# REV001.net
KiCad netlist of a schematic drawn in EAGLE
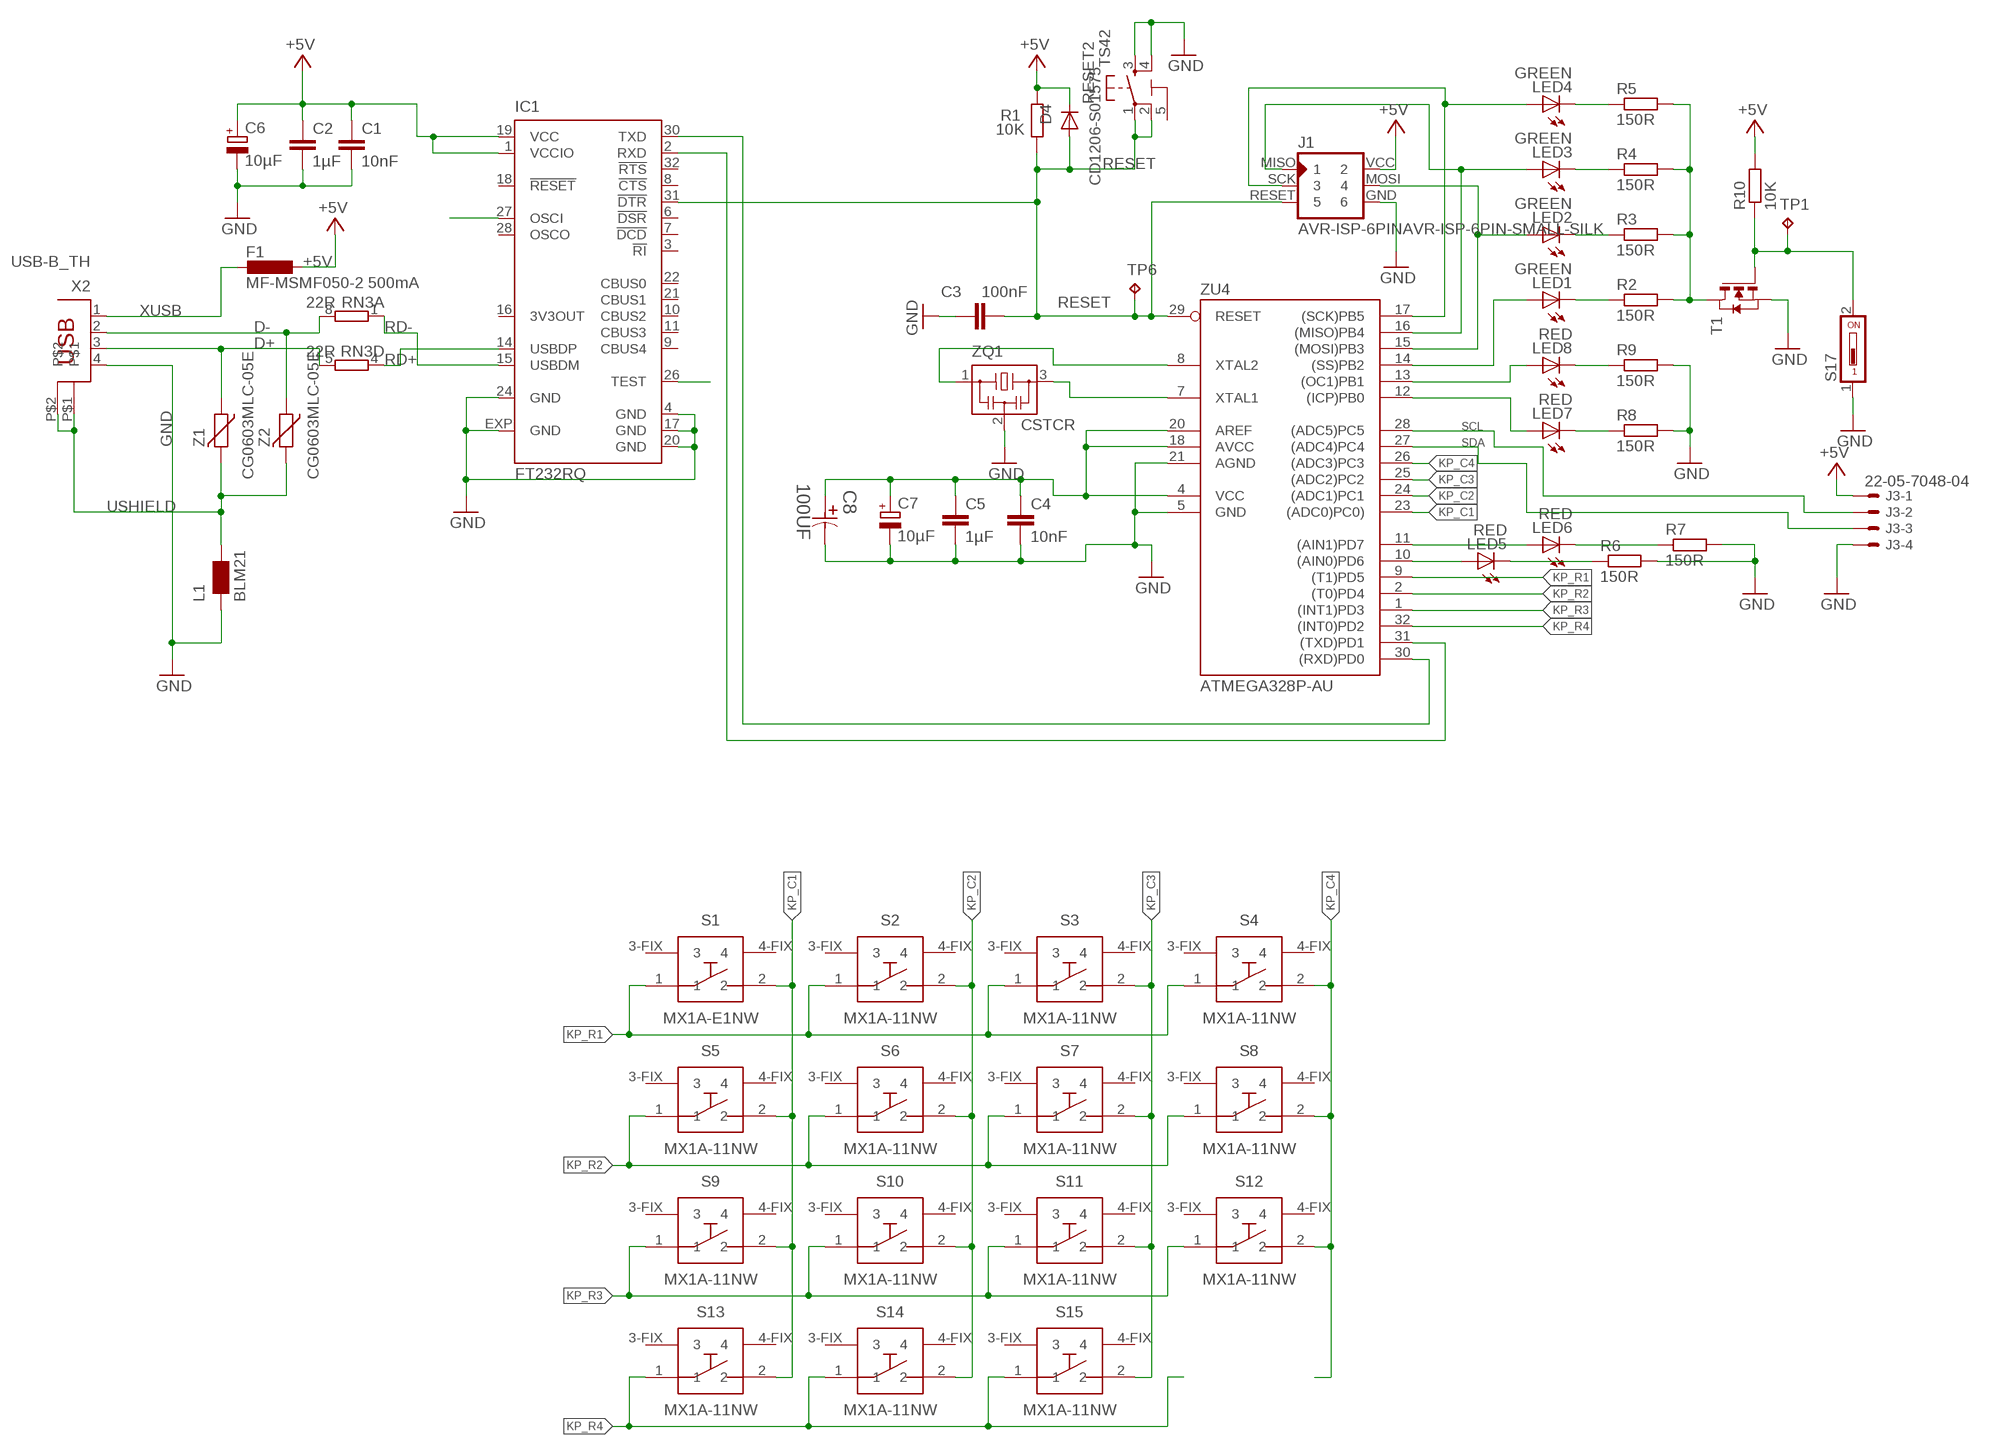
[diagram p0: schematic, sheet 1]

(export (version "E")
  (design (tool "Eeschema 10.0.6"))
  (components
    (comp (ref "C1")
      (value "10nF")
      (footprint "eagle-import:C0603K")
      (libsource (lib "eagle-import") (part "rcl_C-EUC0603K"))
    )
    (comp (ref "C2")
      (value "1µF")
      (footprint "eagle-import:C0603K")
      (libsource (lib "eagle-import") (part "rcl_C-EUC0603K"))
    )
    (comp (ref "C3")
      (value "100nF")
      (footprint "eagle-import:C0603-ROUND")
      (libsource (lib "eagle-import") (part "C-EUC0603"))
    )
    (comp (ref "C4")
      (value "10nF")
      (footprint "eagle-import:C0603K")
      (libsource (lib "eagle-import") (part "rcl_C-EUC0603K"))
    )
    (comp (ref "C5")
      (value "1µF")
      (footprint "eagle-import:C0603K")
      (libsource (lib "eagle-import") (part "rcl_C-EUC0603K"))
    )
    (comp (ref "C6")
      (value "10µF")
      (footprint "eagle-import:SMC_B")
      (libsource (lib "eagle-import") (part "CPOL-EUSMCB"))
    )
    (comp (ref "C7")
      (value "10µF")
      (footprint "eagle-import:SMC_B")
      (libsource (lib "eagle-import") (part "CPOL-EUSMCB"))
    )
    (comp (ref "C8")
      (value "100UF")
      (footprint "eagle-import:CAPAE430X610N")
      (fields (field (name "MPN") "EEE-FT0J101AR ") (field (name "TOLERANCE") "±20 %"))
      (libsource (lib "eagle-import") (part "EEE--CASE-BFT0J101AR"))
    )
    (comp (ref "D4")
      (value "CD1206-S01575")
      (footprint "eagle-import:MINIMELF")
      (libsource (lib "eagle-import") (part "DIODE-MINIMELF"))
    )
    (comp (ref "F1")
      (value "MF-MSMF050-2 500mA")
      (footprint "eagle-import:L1812")
      (libsource (lib "eagle-import") (part "L-EUL1812"))
    )
    (comp (ref "IC1")
      (value "FT232RQ")
      (footprint "eagle-import:QFN32")
      (libsource (lib "eagle-import") (part "FT232RQ"))
    )
    (comp (ref "J1")
      (value "AVR-ISP-6PINAVR-ISP-6PIN-SMALL-SILK")
      (footprint "eagle-import:AVR-ISP-6PIN-SMAILL-SILK")
      (libsource (lib "eagle-import") (part "AVR-ISP-6PINAVR-ISP-6PIN-SMALL-SILK"))
    )
    (comp (ref "J3")
      (value "22-05-7048-04")
      (footprint "eagle-import:7395-04")
      (libsource (lib "eagle-import") (part "22-?-0405-7048"))
    )
    (comp (ref "L1")
      (value "BLM21")
      (footprint "eagle-import:0805")
      (libsource (lib "eagle-import") (part "WE-CBF_0805"))
    )
    (comp (ref "LED1")
      (value "GREEN")
      (footprint "eagle-import:P-LCC-2")
      (libsource (lib "eagle-import") (part "LEDP-LCC-2"))
    )
    (comp (ref "LED2")
      (value "GREEN")
      (footprint "eagle-import:P-LCC-2")
      (libsource (lib "eagle-import") (part "LEDP-LCC-2"))
    )
    (comp (ref "LED3")
      (value "GREEN")
      (footprint "eagle-import:P-LCC-2")
      (libsource (lib "eagle-import") (part "LEDP-LCC-2"))
    )
    (comp (ref "LED4")
      (value "GREEN")
      (footprint "eagle-import:P-LCC-2")
      (libsource (lib "eagle-import") (part "LEDP-LCC-2"))
    )
    (comp (ref "LED5")
      (value "RED")
      (footprint "eagle-import:P-LCC-2")
      (libsource (lib "eagle-import") (part "LEDP-LCC-2"))
    )
    (comp (ref "LED6")
      (value "RED")
      (footprint "eagle-import:P-LCC-2")
      (libsource (lib "eagle-import") (part "LEDP-LCC-2"))
    )
    (comp (ref "LED7")
      (value "RED")
      (footprint "eagle-import:P-LCC-2")
      (libsource (lib "eagle-import") (part "LEDP-LCC-2"))
    )
    (comp (ref "LED8")
      (value "RED")
      (footprint "eagle-import:P-LCC-2")
      (libsource (lib "eagle-import") (part "LEDP-LCC-2"))
    )
    (comp (ref "R1")
      (value "10K")
      (footprint "eagle-import:R0805")
      (libsource (lib "eagle-import") (part "R-EU_R0805"))
    )
    (comp (ref "R2")
      (value "150R")
      (footprint "eagle-import:R0805")
      (libsource (lib "eagle-import") (part "rcl_R-EU_R0805"))
    )
    (comp (ref "R3")
      (value "150R")
      (footprint "eagle-import:R0805")
      (libsource (lib "eagle-import") (part "rcl_R-EU_R0805"))
    )
    (comp (ref "R4")
      (value "150R")
      (footprint "eagle-import:R0805")
      (libsource (lib "eagle-import") (part "rcl_R-EU_R0805"))
    )
    (comp (ref "R5")
      (value "150R")
      (footprint "eagle-import:R0805")
      (libsource (lib "eagle-import") (part "rcl_R-EU_R0805"))
    )
    (comp (ref "R6")
      (value "150R")
      (footprint "eagle-import:R0805")
      (libsource (lib "eagle-import") (part "rcl_R-EU_R0805"))
    )
    (comp (ref "R7")
      (value "150R")
      (footprint "eagle-import:R0805")
      (libsource (lib "eagle-import") (part "rcl_R-EU_R0805"))
    )
    (comp (ref "R8")
      (value "150R")
      (footprint "eagle-import:R0805")
      (libsource (lib "eagle-import") (part "rcl_R-EU_R0805"))
    )
    (comp (ref "R9")
      (value "150R")
      (footprint "eagle-import:R0805")
      (libsource (lib "eagle-import") (part "rcl_R-EU_R0805"))
    )
    (comp (ref "R10")
      (value "10K")
      (footprint "eagle-import:R0805")
      (libsource (lib "eagle-import") (part "rcl_R-EU_R0805"))
    )
    (comp (ref "RESET2")
      (value "TS42")
      (footprint "eagle-import:TS42")
      (libsource (lib "eagle-import") (part "TS42"))
    )
    (comp (ref "RN3")
      (value "22R")
      (footprint "eagle-import:CAY16")
      (libsource (lib "eagle-import") (part "4R-NCAY16"))
    )
    (comp (ref "S1")
      (value "MX1A-E1NW")
      (footprint "eagle-import:MX1A-11NW_1")
      (fields (field (name "MANUFACTURER_PART_NUMBER") "MX1A-11NW"))
      (libsource (lib "eagle-import") (part "MX1A-11NW"))
    )
    (comp (ref "S2")
      (value "MX1A-11NW")
      (footprint "eagle-import:MX1A-11NW_1")
      (libsource (lib "eagle-import") (part "MX1A-11NW"))
    )
    (comp (ref "S3")
      (value "MX1A-11NW")
      (footprint "eagle-import:MX1A-11NW_1")
      (libsource (lib "eagle-import") (part "MX1A-11NW"))
    )
    (comp (ref "S4")
      (value "MX1A-11NW")
      (footprint "eagle-import:MX1A-11NW_1")
      (libsource (lib "eagle-import") (part "MX1A-11NW"))
    )
    (comp (ref "S5")
      (value "MX1A-11NW")
      (footprint "eagle-import:MX1A-11NW_1")
      (libsource (lib "eagle-import") (part "MX1A-11NW"))
    )
    (comp (ref "S6")
      (value "MX1A-11NW")
      (footprint "eagle-import:MX1A-11NW_1")
      (libsource (lib "eagle-import") (part "MX1A-11NW"))
    )
    (comp (ref "S7")
      (value "MX1A-11NW")
      (footprint "eagle-import:MX1A-11NW_1")
      (libsource (lib "eagle-import") (part "MX1A-11NW"))
    )
    (comp (ref "S8")
      (value "MX1A-11NW")
      (footprint "eagle-import:MX1A-11NW_1")
      (libsource (lib "eagle-import") (part "MX1A-11NW"))
    )
    (comp (ref "S9")
      (value "MX1A-11NW")
      (footprint "eagle-import:MX1A-11NW_1")
      (libsource (lib "eagle-import") (part "MX1A-11NW"))
    )
    (comp (ref "S10")
      (value "MX1A-11NW")
      (footprint "eagle-import:MX1A-11NW_1")
      (libsource (lib "eagle-import") (part "MX1A-11NW"))
    )
    (comp (ref "S11")
      (value "MX1A-11NW")
      (footprint "eagle-import:MX1A-11NW_1")
      (libsource (lib "eagle-import") (part "MX1A-11NW"))
    )
    (comp (ref "S12")
      (value "MX1A-11NW")
      (footprint "eagle-import:MX1A-11NW_1")
      (libsource (lib "eagle-import") (part "MX1A-11NW"))
    )
    (comp (ref "S13")
      (value "MX1A-11NW")
      (footprint "eagle-import:MX1A-11NW_1")
      (libsource (lib "eagle-import") (part "MX1A-11NW"))
    )
    (comp (ref "S14")
      (value "MX1A-11NW")
      (footprint "eagle-import:MX1A-11NW_1")
      (libsource (lib "eagle-import") (part "MX1A-11NW"))
    )
    (comp (ref "S15")
      (value "MX1A-11NW")
      (footprint "eagle-import:MX1A-11NW_1")
      (libsource (lib "eagle-import") (part "MX1A-11NW"))
    )
    (comp (ref "S17")
      (value "DS01")
      (footprint "eagle-import:DS-01")
      (libsource (lib "eagle-import") (part "DS01"))
    )
    (comp (ref "T1")
      (value "NMOSSOT23")
      (footprint "eagle-import:SOT-23")
      (libsource (lib "eagle-import") (part "NMOSSOT23"))
    )
    (comp (ref "TP1")
      (value "TPB1,27")
      (footprint "eagle-import:B1,27")
      (libsource (lib "eagle-import") (part "TPB1,27"))
    )
    (comp (ref "TP6")
      (value "TPB1,27")
      (footprint "eagle-import:B1,27")
      (libsource (lib "eagle-import") (part "TPB1,27"))
    )
    (comp (ref "X2")
      (value "USB-B_TH")
      (footprint "eagle-import:PN61729")
      (libsource (lib "eagle-import") (part "PN61729"))
    )
    (comp (ref "Z1")
      (value "CG0603MLC-05E")
      (footprint "eagle-import:CT_CN0603")
      (libsource (lib "eagle-import") (part "VARISTORCN0603"))
    )
    (comp (ref "Z2")
      (value "CG0603MLC-05E")
      (footprint "eagle-import:CT_CN0603")
      (libsource (lib "eagle-import") (part "VARISTORCN0603"))
    )
    (comp (ref "ZQ1")
      (value "CSTCR")
      (footprint "eagle-import:CSTER12M")
      (libsource (lib "eagle-import") (part "CSTC?R"))
    )
    (comp (ref "ZU4")
      (value "ATMEGA328P-AU")
      (footprint "eagle-import:TQFP32-08")
      (libsource (lib "eagle-import") (part "ATMEGA328P-AU"))
    )
  )
  (nets
    (net (code "1") (name "+5V") (class "Default")
      (node (ref "C1") (pin "1") (pinfunction "1_1") (pintype "passive"))
      (node (ref "C2") (pin "1") (pinfunction "1_1") (pintype "passive"))
      (node (ref "C4") (pin "1") (pinfunction "1_1") (pintype "passive"))
      (node (ref "C5") (pin "1") (pinfunction "1_1") (pintype "passive"))
      (node (ref "C6") (pin "+") (pinfunction "+_+") (pintype "passive"))
      (node (ref "C7") (pin "+") (pinfunction "+_+") (pintype "passive"))
      (node (ref "C8") (pin "1") (pinfunction "1_1") (pintype "passive"))
      (node (ref "D4") (pin "C") (pinfunction "C_C") (pintype "passive"))
      (node (ref "F1") (pin "1") (pinfunction "1_1") (pintype "passive"))
      (node (ref "IC1") (pin "1") (pinfunction "VCCIO_1") (pintype "power_in"))
      (node (ref "IC1") (pin "19") (pinfunction "VCC_19") (pintype "power_in"))
      (node (ref "J1") (pin "VCC") (pinfunction "2_VCC") (pintype "passive"))
      (node (ref "J3") (pin "1") (pinfunction "S_1") (pintype "passive"))
      (node (ref "R1") (pin "2") (pinfunction "2_2") (pintype "passive"))
      (node (ref "R10") (pin "2") (pinfunction "2_2") (pintype "passive"))
      (node (ref "ZU4") (pin "18") (pinfunction "AVCC_18") (pintype "power_in"))
      (node (ref "ZU4") (pin "20") (pinfunction "AREF_20") (pintype "passive"))
      (node (ref "ZU4") (pin "4") (pinfunction "VCC_4") (pintype "power_in"))
    )
    (net (code "2") (name "/5-GND") (class "Default")
      (node (ref "RESET2") (pin "5") (pinfunction "5-GND_5") (pintype "power_in"))
    )
    (net (code "3") (name "/D+") (class "Default")
      (node (ref "RN3") (pin "5") (pinfunction "2_5") (pintype "passive"))
      (node (ref "X2") (pin "3") (pinfunction "3_3") (pintype "bidirectional"))
      (node (ref "Z1") (pin "1") (pinfunction "1_1") (pintype "passive"))
    )
    (net (code "4") (name "/D-") (class "Default")
      (node (ref "RN3") (pin "8") (pinfunction "2_8") (pintype "passive"))
      (node (ref "X2") (pin "2") (pinfunction "2_2") (pintype "bidirectional"))
      (node (ref "Z2") (pin "1") (pinfunction "1_1") (pintype "passive"))
    )
    (net (code "5") (name "/RD+") (class "Default")
      (node (ref "IC1") (pin "14") (pinfunction "USBDP_14") (pintype "bidirectional"))
      (node (ref "RN3") (pin "4") (pinfunction "1_4") (pintype "passive"))
    )
    (net (code "6") (name "/RD-") (class "Default")
      (node (ref "IC1") (pin "15") (pinfunction "USBDM_15") (pintype "bidirectional"))
      (node (ref "RN3") (pin "1") (pinfunction "1_1") (pintype "passive"))
    )
    (net (code "7") (name "/RESET") (class "Default")
      (node (ref "C3") (pin "1") (pinfunction "1_1") (pintype "passive"))
      (node (ref "D4") (pin "A") (pinfunction "A_A") (pintype "passive"))
      (node (ref "IC1") (pin "31") (pinfunction "~{DTR}_31") (pintype "output"))
      (node (ref "J1") (pin "RESET") (pinfunction "5_RESET") (pintype "passive"))
      (node (ref "R1") (pin "1") (pinfunction "1_1") (pintype "passive"))
      (node (ref "RESET2") (pin "1") (pinfunction "1_1") (pintype "passive"))
      (node (ref "RESET2") (pin "2") (pinfunction "2_2") (pintype "passive"))
      (node (ref "TP6") (pin "TP") (pinfunction "TP_TP") (pintype "input"))
      (node (ref "ZU4") (pin "29") (pinfunction "RESET_29") (pintype "input"))
    )
    (net (code "8") (name "/SCL") (class "Default")
      (node (ref "J3") (pin "2") (pinfunction "S_2") (pintype "passive"))
      (node (ref "ZU4") (pin "28") (pinfunction "(ADC5)PC5_28") (pintype "bidirectional"))
    )
    (net (code "9") (name "/SDA") (class "Default")
      (node (ref "J3") (pin "3") (pinfunction "S_3") (pintype "passive"))
      (node (ref "ZU4") (pin "27") (pinfunction "(ADC4)PC4_27") (pintype "bidirectional"))
    )
    (net (code "10") (name "/USHIELD") (class "Default")
      (node (ref "L1") (pin "2") (pinfunction "2_2") (pintype "passive"))
      (node (ref "X2") (pin "P$1") (pinfunction "P$1_P$1") (pintype "bidirectional"))
      (node (ref "X2") (pin "P$2") (pinfunction "P$2_P$2") (pintype "bidirectional"))
      (node (ref "Z1") (pin "2") (pinfunction "2_2") (pintype "passive"))
      (node (ref "Z2") (pin "2") (pinfunction "2_2") (pintype "passive"))
    )
    (net (code "11") (name "/XUSB") (class "Default")
      (node (ref "F1") (pin "2") (pinfunction "2_2") (pintype "passive"))
      (node (ref "X2") (pin "1") (pinfunction "1_1") (pintype "bidirectional"))
    )
    (net (code "12") (name "GND") (class "Default")
      (node (ref "C1") (pin "2") (pinfunction "2_2") (pintype "passive"))
      (node (ref "C2") (pin "2") (pinfunction "2_2") (pintype "passive"))
      (node (ref "C3") (pin "2") (pinfunction "2_2") (pintype "passive"))
      (node (ref "C4") (pin "2") (pinfunction "2_2") (pintype "passive"))
      (node (ref "C5") (pin "2") (pinfunction "2_2") (pintype "passive"))
      (node (ref "C6") (pin "-") (pinfunction "-_-") (pintype "passive"))
      (node (ref "C7") (pin "-") (pinfunction "-_-") (pintype "passive"))
      (node (ref "C8") (pin "2") (pinfunction "2_2") (pintype "passive"))
      (node (ref "IC1") (pin "17") (pinfunction "GND_17") (pintype "power_in"))
      (node (ref "IC1") (pin "20") (pinfunction "GND_20") (pintype "power_in"))
      (node (ref "IC1") (pin "24") (pinfunction "GND_24") (pintype "power_in"))
      (node (ref "IC1") (pin "4") (pinfunction "GND_4") (pintype "power_in"))
      (node (ref "IC1") (pin "EXP") (pinfunction "GND_EXP") (pintype "power_in"))
      (node (ref "J1") (pin "GND") (pinfunction "6_GND") (pintype "passive"))
      (node (ref "J3") (pin "4") (pinfunction "S_4") (pintype "passive"))
      (node (ref "L1") (pin "1") (pinfunction "1_1") (pintype "passive"))
      (node (ref "R6") (pin "2") (pinfunction "2_2") (pintype "passive"))
      (node (ref "R7") (pin "2") (pinfunction "2_2") (pintype "passive"))
      (node (ref "R8") (pin "2") (pinfunction "2_2") (pintype "passive"))
      (node (ref "R9") (pin "2") (pinfunction "2_2") (pintype "passive"))
      (node (ref "RESET2") (pin "3") (pinfunction "3_3") (pintype "passive"))
      (node (ref "RESET2") (pin "4") (pinfunction "4_4") (pintype "passive"))
      (node (ref "S17") (pin "1") (pinfunction "1_1") (pintype "passive"))
      (node (ref "T1") (pin "2") (pinfunction "S_2") (pintype "passive"))
      (node (ref "X2") (pin "4") (pinfunction "4_4") (pintype "bidirectional"))
      (node (ref "ZQ1") (pin "2") (pinfunction "2_2") (pintype "passive"))
      (node (ref "ZU4") (pin "21") (pinfunction "AGND_21") (pintype "power_in"))
      (node (ref "ZU4") (pin "5") (pinfunction "GND_5") (pintype "power_in"))
    )
    (net (code "13") (name "KP_C1") (class "Default")
      (node (ref "S1") (pin "2") (pinfunction "2_2") (pintype "input"))
      (node (ref "S13") (pin "2") (pinfunction "2_2") (pintype "input"))
      (node (ref "S5") (pin "2") (pinfunction "2_2") (pintype "input"))
      (node (ref "S9") (pin "2") (pinfunction "2_2") (pintype "input"))
      (node (ref "ZU4") (pin "23") (pinfunction "(ADC0)PC0)_23") (pintype "bidirectional"))
    )
    (net (code "14") (name "KP_C2") (class "Default")
      (node (ref "S10") (pin "2") (pinfunction "2_2") (pintype "input"))
      (node (ref "S14") (pin "2") (pinfunction "2_2") (pintype "input"))
      (node (ref "S2") (pin "2") (pinfunction "2_2") (pintype "input"))
      (node (ref "S6") (pin "2") (pinfunction "2_2") (pintype "input"))
      (node (ref "ZU4") (pin "24") (pinfunction "(ADC1)PC1_24") (pintype "bidirectional"))
    )
    (net (code "15") (name "KP_C3") (class "Default")
      (node (ref "S11") (pin "2") (pinfunction "2_2") (pintype "input"))
      (node (ref "S15") (pin "2") (pinfunction "2_2") (pintype "input"))
      (node (ref "S3") (pin "2") (pinfunction "2_2") (pintype "input"))
      (node (ref "S7") (pin "2") (pinfunction "2_2") (pintype "input"))
      (node (ref "ZU4") (pin "25") (pinfunction "(ADC2)PC2_25") (pintype "bidirectional"))
    )
    (net (code "16") (name "KP_C4") (class "Default")
      (node (ref "S12") (pin "2") (pinfunction "2_2") (pintype "input"))
      (node (ref "S4") (pin "2") (pinfunction "2_2") (pintype "input"))
      (node (ref "S8") (pin "2") (pinfunction "2_2") (pintype "input"))
      (node (ref "ZU4") (pin "26") (pinfunction "(ADC3)PC3_26") (pintype "bidirectional"))
    )
    (net (code "17") (name "KP_R1") (class "Default")
      (node (ref "S1") (pin "1") (pinfunction "1_1") (pintype "input"))
      (node (ref "S2") (pin "1") (pinfunction "1_1") (pintype "input"))
      (node (ref "S3") (pin "1") (pinfunction "1_1") (pintype "input"))
      (node (ref "S4") (pin "1") (pinfunction "1_1") (pintype "input"))
      (node (ref "ZU4") (pin "9") (pinfunction "(T1)PD5_9") (pintype "bidirectional"))
    )
    (net (code "18") (name "KP_R2") (class "Default")
      (node (ref "S5") (pin "1") (pinfunction "1_1") (pintype "input"))
      (node (ref "S6") (pin "1") (pinfunction "1_1") (pintype "input"))
      (node (ref "S7") (pin "1") (pinfunction "1_1") (pintype "input"))
      (node (ref "S8") (pin "1") (pinfunction "1_1") (pintype "input"))
      (node (ref "ZU4") (pin "2") (pinfunction "(T0)PD4_2") (pintype "bidirectional"))
    )
    (net (code "19") (name "KP_R3") (class "Default")
      (node (ref "S10") (pin "1") (pinfunction "1_1") (pintype "input"))
      (node (ref "S11") (pin "1") (pinfunction "1_1") (pintype "input"))
      (node (ref "S12") (pin "1") (pinfunction "1_1") (pintype "input"))
      (node (ref "S9") (pin "1") (pinfunction "1_1") (pintype "input"))
      (node (ref "ZU4") (pin "1") (pinfunction "(INT1)PD3_1") (pintype "bidirectional"))
    )
    (net (code "20") (name "KP_R4") (class "Default")
      (node (ref "S13") (pin "1") (pinfunction "1_1") (pintype "input"))
      (node (ref "S14") (pin "1") (pinfunction "1_1") (pintype "input"))
      (node (ref "S15") (pin "1") (pinfunction "1_1") (pintype "input"))
      (node (ref "ZU4") (pin "32") (pinfunction "(INT0)PD2_32") (pintype "bidirectional"))
    )
    (net (code "21") (name "Net-(IC1-RXD)") (class "Default")
      (node (ref "IC1") (pin "2") (pinfunction "RXD_2") (pintype "input"))
      (node (ref "ZU4") (pin "31") (pinfunction "(TXD)PD1_31") (pintype "bidirectional"))
    )
    (net (code "22") (name "Net-(IC1-TXD)") (class "Default")
      (node (ref "IC1") (pin "30") (pinfunction "TXD_30") (pintype "output"))
      (node (ref "ZU4") (pin "30") (pinfunction "(RXD)PD0_30") (pintype "bidirectional"))
    )
    (net (code "23") (name "Net-(J1-1)") (class "Default")
      (node (ref "J1") (pin "MISO") (pinfunction "1_MISO") (pintype "passive"))
      (node (ref "LED3") (pin "A") (pinfunction "A_A") (pintype "passive"))
      (node (ref "ZU4") (pin "16") (pinfunction "(MISO)PB4_16") (pintype "bidirectional"))
    )
    (net (code "24") (name "Net-(J1-3)") (class "Default")
      (node (ref "J1") (pin "SCK") (pinfunction "3_SCK") (pintype "passive"))
      (node (ref "LED4") (pin "A") (pinfunction "A_A") (pintype "passive"))
      (node (ref "ZU4") (pin "17") (pinfunction "(SCK)PB5_17") (pintype "bidirectional"))
    )
    (net (code "25") (name "Net-(J1-4)") (class "Default")
      (node (ref "J1") (pin "MOSI") (pinfunction "4_MOSI") (pintype "passive"))
      (node (ref "LED2") (pin "A") (pinfunction "A_A") (pintype "passive"))
      (node (ref "ZU4") (pin "15") (pinfunction "(MOSI)PB3_15") (pintype "bidirectional"))
    )
    (net (code "26") (name "Net-(LED1-PadC)") (class "Default")
      (node (ref "LED1") (pin "C") (pinfunction "C_C") (pintype "passive"))
      (node (ref "R2") (pin "1") (pinfunction "1_1") (pintype "passive"))
    )
    (net (code "27") (name "Net-(LED2-PadC)") (class "Default")
      (node (ref "LED2") (pin "C") (pinfunction "C_C") (pintype "passive"))
      (node (ref "R3") (pin "1") (pinfunction "1_1") (pintype "passive"))
    )
    (net (code "28") (name "Net-(LED3-PadC)") (class "Default")
      (node (ref "LED3") (pin "C") (pinfunction "C_C") (pintype "passive"))
      (node (ref "R4") (pin "1") (pinfunction "1_1") (pintype "passive"))
    )
    (net (code "29") (name "Net-(LED4-PadC)") (class "Default")
      (node (ref "LED4") (pin "C") (pinfunction "C_C") (pintype "passive"))
      (node (ref "R5") (pin "1") (pinfunction "1_1") (pintype "passive"))
    )
    (net (code "30") (name "Net-(LED5-PadC)") (class "Default")
      (node (ref "LED5") (pin "C") (pinfunction "C_C") (pintype "passive"))
      (node (ref "R6") (pin "1") (pinfunction "1_1") (pintype "passive"))
    )
    (net (code "31") (name "Net-(LED6-PadC)") (class "Default")
      (node (ref "LED6") (pin "C") (pinfunction "C_C") (pintype "passive"))
      (node (ref "R7") (pin "1") (pinfunction "1_1") (pintype "passive"))
    )
    (net (code "32") (name "Net-(LED7-PadC)") (class "Default")
      (node (ref "LED7") (pin "C") (pinfunction "C_C") (pintype "passive"))
      (node (ref "R8") (pin "1") (pinfunction "1_1") (pintype "passive"))
    )
    (net (code "33") (name "Net-(LED8-PadC)") (class "Default")
      (node (ref "LED8") (pin "C") (pinfunction "C_C") (pintype "passive"))
      (node (ref "R9") (pin "1") (pinfunction "1_1") (pintype "passive"))
    )
    (net (code "34") (name "Net-(T1-D)") (class "Default")
      (node (ref "R2") (pin "2") (pinfunction "2_2") (pintype "passive"))
      (node (ref "R3") (pin "2") (pinfunction "2_2") (pintype "passive"))
      (node (ref "R4") (pin "2") (pinfunction "2_2") (pintype "passive"))
      (node (ref "R5") (pin "2") (pinfunction "2_2") (pintype "passive"))
      (node (ref "T1") (pin "1") (pinfunction "D_1") (pintype "passive"))
    )
    (net (code "35") (name "Net-(T1-G)") (class "Default")
      (node (ref "R10") (pin "1") (pinfunction "1_1") (pintype "passive"))
      (node (ref "S17") (pin "2") (pinfunction "2_2") (pintype "passive"))
      (node (ref "T1") (pin "3") (pinfunction "G_3") (pintype "passive"))
      (node (ref "TP1") (pin "TP") (pinfunction "TP_TP") (pintype "input"))
    )
    (net (code "36") (name "Net-(ZU4-(AIN0)PD6)") (class "Default")
      (node (ref "LED5") (pin "A") (pinfunction "A_A") (pintype "passive"))
      (node (ref "ZU4") (pin "10") (pinfunction "(AIN0)PD6_10") (pintype "bidirectional"))
    )
    (net (code "37") (name "Net-(ZU4-(AIN1)PD7)") (class "Default")
      (node (ref "LED6") (pin "A") (pinfunction "A_A") (pintype "passive"))
      (node (ref "ZU4") (pin "11") (pinfunction "(AIN1)PD7_11") (pintype "bidirectional"))
    )
    (net (code "38") (name "Net-(ZU4-(ICP)PB0)") (class "Default")
      (node (ref "LED7") (pin "A") (pinfunction "A_A") (pintype "passive"))
      (node (ref "ZU4") (pin "12") (pinfunction "(ICP)PB0_12") (pintype "bidirectional"))
    )
    (net (code "39") (name "Net-(ZU4-(OC1)PB1)") (class "Default")
      (node (ref "LED8") (pin "A") (pinfunction "A_A") (pintype "passive"))
      (node (ref "ZU4") (pin "13") (pinfunction "(OC1)PB1_13") (pintype "bidirectional"))
    )
    (net (code "40") (name "Net-(ZU4-(SS)PB2)") (class "Default")
      (node (ref "LED1") (pin "A") (pinfunction "A_A") (pintype "passive"))
      (node (ref "ZU4") (pin "14") (pinfunction "(SS)PB2_14") (pintype "bidirectional"))
    )
    (net (code "41") (name "Net-(ZU4-XTAL1)") (class "Default")
      (node (ref "ZQ1") (pin "3") (pinfunction "3_3") (pintype "passive"))
      (node (ref "ZU4") (pin "7") (pinfunction "XTAL1_7") (pintype "bidirectional"))
    )
    (net (code "42") (name "Net-(ZU4-XTAL2)") (class "Default")
      (node (ref "ZQ1") (pin "1") (pinfunction "1_1") (pintype "passive"))
      (node (ref "ZU4") (pin "8") (pinfunction "XTAL2_8") (pintype "bidirectional"))
    )
    (net (code "43") (name "unconnected-(IC1-3V3OUT-Pad16)") (class "Default")
      (node (ref "IC1") (pin "16") (pinfunction "3V3OUT_16") (pintype "output"))
    )
    (net (code "44") (name "unconnected-(IC1-CBUS0-Pad22)") (class "Default")
      (node (ref "IC1") (pin "22") (pinfunction "CBUS0_22") (pintype "bidirectional"))
    )
    (net (code "45") (name "unconnected-(IC1-CBUS1-Pad21)") (class "Default")
      (node (ref "IC1") (pin "21") (pinfunction "CBUS1_21") (pintype "bidirectional"))
    )
    (net (code "46") (name "unconnected-(IC1-CBUS2-Pad10)") (class "Default")
      (node (ref "IC1") (pin "10") (pinfunction "CBUS2_10") (pintype "bidirectional"))
    )
    (net (code "47") (name "unconnected-(IC1-CBUS3-Pad11)") (class "Default")
      (node (ref "IC1") (pin "11") (pinfunction "CBUS3_11") (pintype "bidirectional"))
    )
    (net (code "48") (name "unconnected-(IC1-CBUS4-Pad9)") (class "Default")
      (node (ref "IC1") (pin "9") (pinfunction "CBUS4_9") (pintype "bidirectional"))
    )
    (net (code "49") (name "unconnected-(IC1-OSCI-Pad27)") (class "Default")
      (node (ref "IC1") (pin "27") (pinfunction "OSCI_27") (pintype "input"))
    )
    (net (code "50") (name "unconnected-(IC1-OSCO-Pad28)") (class "Default")
      (node (ref "IC1") (pin "28") (pinfunction "OSCO_28") (pintype "output"))
    )
    (net (code "51") (name "unconnected-(IC1-TEST-Pad26)") (class "Default")
      (node (ref "IC1") (pin "26") (pinfunction "TEST_26") (pintype "input"))
    )
    (net (code "52") (name "unconnected-(IC1-~{CTS}-Pad8)") (class "Default")
      (node (ref "IC1") (pin "8") (pinfunction "~{CTS}_8") (pintype "input"))
    )
    (net (code "53") (name "unconnected-(IC1-~{DCD}-Pad7)") (class "Default")
      (node (ref "IC1") (pin "7") (pinfunction "~{DCD}_7") (pintype "input"))
    )
    (net (code "54") (name "unconnected-(IC1-~{DSR}-Pad6)") (class "Default")
      (node (ref "IC1") (pin "6") (pinfunction "~{DSR}_6") (pintype "input"))
    )
    (net (code "55") (name "unconnected-(IC1-~{RESET}-Pad18)") (class "Default")
      (node (ref "IC1") (pin "18") (pinfunction "~{RESET}_18") (pintype "input"))
    )
    (net (code "56") (name "unconnected-(IC1-~{RI}-Pad3)") (class "Default")
      (node (ref "IC1") (pin "3") (pinfunction "~{RI}_3") (pintype "input"))
    )
    (net (code "57") (name "unconnected-(IC1-~{RTS}-Pad32)") (class "Default")
      (node (ref "IC1") (pin "32") (pinfunction "~{RTS}_32") (pintype "output"))
    )
    (net (code "58") (name "unconnected-(S1-3-Pad3-FIX)") (class "Default")
      (node (ref "S1") (pin "3-FIX") (pinfunction "3_3-FIX") (pintype "input"))
    )
    (net (code "59") (name "unconnected-(S1-4-Pad4-FIX)") (class "Default")
      (node (ref "S1") (pin "4-FIX") (pinfunction "4_4-FIX") (pintype "input"))
    )
    (net (code "60") (name "unconnected-(S2-3-Pad3-FIX)") (class "Default")
      (node (ref "S2") (pin "3-FIX") (pinfunction "3_3-FIX") (pintype "input"))
    )
    (net (code "61") (name "unconnected-(S2-4-Pad4-FIX)") (class "Default")
      (node (ref "S2") (pin "4-FIX") (pinfunction "4_4-FIX") (pintype "input"))
    )
    (net (code "62") (name "unconnected-(S3-3-Pad3-FIX)") (class "Default")
      (node (ref "S3") (pin "3-FIX") (pinfunction "3_3-FIX") (pintype "input"))
    )
    (net (code "63") (name "unconnected-(S3-4-Pad4-FIX)") (class "Default")
      (node (ref "S3") (pin "4-FIX") (pinfunction "4_4-FIX") (pintype "input"))
    )
    (net (code "64") (name "unconnected-(S4-3-Pad3-FIX)") (class "Default")
      (node (ref "S4") (pin "3-FIX") (pinfunction "3_3-FIX") (pintype "input"))
    )
    (net (code "65") (name "unconnected-(S4-4-Pad4-FIX)") (class "Default")
      (node (ref "S4") (pin "4-FIX") (pinfunction "4_4-FIX") (pintype "input"))
    )
    (net (code "66") (name "unconnected-(S5-3-Pad3-FIX)") (class "Default")
      (node (ref "S5") (pin "3-FIX") (pinfunction "3_3-FIX") (pintype "input"))
    )
    (net (code "67") (name "unconnected-(S5-4-Pad4-FIX)") (class "Default")
      (node (ref "S5") (pin "4-FIX") (pinfunction "4_4-FIX") (pintype "input"))
    )
    (net (code "68") (name "unconnected-(S6-3-Pad3-FIX)") (class "Default")
      (node (ref "S6") (pin "3-FIX") (pinfunction "3_3-FIX") (pintype "input"))
    )
    (net (code "69") (name "unconnected-(S6-4-Pad4-FIX)") (class "Default")
      (node (ref "S6") (pin "4-FIX") (pinfunction "4_4-FIX") (pintype "input"))
    )
    (net (code "70") (name "unconnected-(S7-3-Pad3-FIX)") (class "Default")
      (node (ref "S7") (pin "3-FIX") (pinfunction "3_3-FIX") (pintype "input"))
    )
    (net (code "71") (name "unconnected-(S7-4-Pad4-FIX)") (class "Default")
      (node (ref "S7") (pin "4-FIX") (pinfunction "4_4-FIX") (pintype "input"))
    )
    (net (code "72") (name "unconnected-(S8-3-Pad3-FIX)") (class "Default")
      (node (ref "S8") (pin "3-FIX") (pinfunction "3_3-FIX") (pintype "input"))
    )
    (net (code "73") (name "unconnected-(S8-4-Pad4-FIX)") (class "Default")
      (node (ref "S8") (pin "4-FIX") (pinfunction "4_4-FIX") (pintype "input"))
    )
    (net (code "74") (name "unconnected-(S9-3-Pad3-FIX)") (class "Default")
      (node (ref "S9") (pin "3-FIX") (pinfunction "3_3-FIX") (pintype "input"))
    )
    (net (code "75") (name "unconnected-(S9-4-Pad4-FIX)") (class "Default")
      (node (ref "S9") (pin "4-FIX") (pinfunction "4_4-FIX") (pintype "input"))
    )
    (net (code "76") (name "unconnected-(S10-3-Pad3-FIX)") (class "Default")
      (node (ref "S10") (pin "3-FIX") (pinfunction "3_3-FIX") (pintype "input"))
    )
    (net (code "77") (name "unconnected-(S10-4-Pad4-FIX)") (class "Default")
      (node (ref "S10") (pin "4-FIX") (pinfunction "4_4-FIX") (pintype "input"))
    )
    (net (code "78") (name "unconnected-(S11-3-Pad3-FIX)") (class "Default")
      (node (ref "S11") (pin "3-FIX") (pinfunction "3_3-FIX") (pintype "input"))
    )
    (net (code "79") (name "unconnected-(S11-4-Pad4-FIX)") (class "Default")
      (node (ref "S11") (pin "4-FIX") (pinfunction "4_4-FIX") (pintype "input"))
    )
    (net (code "80") (name "unconnected-(S12-3-Pad3-FIX)") (class "Default")
      (node (ref "S12") (pin "3-FIX") (pinfunction "3_3-FIX") (pintype "input"))
    )
    (net (code "81") (name "unconnected-(S12-4-Pad4-FIX)") (class "Default")
      (node (ref "S12") (pin "4-FIX") (pinfunction "4_4-FIX") (pintype "input"))
    )
    (net (code "82") (name "unconnected-(S13-3-Pad3-FIX)") (class "Default")
      (node (ref "S13") (pin "3-FIX") (pinfunction "3_3-FIX") (pintype "input"))
    )
    (net (code "83") (name "unconnected-(S13-4-Pad4-FIX)") (class "Default")
      (node (ref "S13") (pin "4-FIX") (pinfunction "4_4-FIX") (pintype "input"))
    )
    (net (code "84") (name "unconnected-(S14-3-Pad3-FIX)") (class "Default")
      (node (ref "S14") (pin "3-FIX") (pinfunction "3_3-FIX") (pintype "input"))
    )
    (net (code "85") (name "unconnected-(S14-4-Pad4-FIX)") (class "Default")
      (node (ref "S14") (pin "4-FIX") (pinfunction "4_4-FIX") (pintype "input"))
    )
    (net (code "86") (name "unconnected-(S15-3-Pad3-FIX)") (class "Default")
      (node (ref "S15") (pin "3-FIX") (pinfunction "3_3-FIX") (pintype "input"))
    )
    (net (code "87") (name "unconnected-(S15-4-Pad4-FIX)") (class "Default")
      (node (ref "S15") (pin "4-FIX") (pinfunction "4_4-FIX") (pintype "input"))
    )
  )
)
